# ManualBot.net
KiCad netlist of a schematic drawn in EAGLE
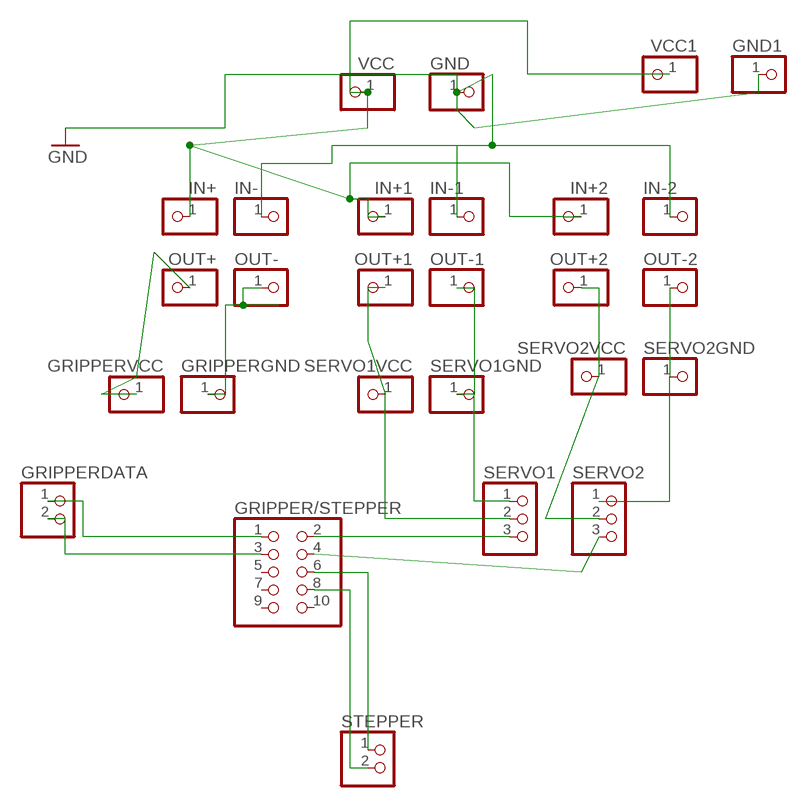
[diagram p0: schematic, sheet 1]

(export (version "E")
  (design (tool "Eeschema 10.0.6"))
  (components
    (comp (ref "GND")
      (value "PINHD-1X1")
      (footprint "eagle-import:1X01")
      (libsource (lib "eagle-import") (part "PINHD-1X1"))
    )
    (comp (ref "GND1")
      (value "PINHD-1X1")
      (footprint "eagle-import:1X01")
      (libsource (lib "eagle-import") (part "PINHD-1X1"))
    )
    (comp (ref "GRIPPER/STEPPER")
      (value "PINHD-2X5")
      (footprint "eagle-import:2X05")
      (libsource (lib "eagle-import") (part "PINHD-2X5"))
    )
    (comp (ref "GRIPPERDATA")
      (value "PINHD-1X2")
      (footprint "eagle-import:1X02")
      (libsource (lib "eagle-import") (part "PINHD-1X2"))
    )
    (comp (ref "GRIPPERGND")
      (value "PINHD-1X1")
      (footprint "eagle-import:1X01")
      (libsource (lib "eagle-import") (part "PINHD-1X1"))
    )
    (comp (ref "GRIPPERVCC")
      (value "PINHD-1X1")
      (footprint "eagle-import:1X01")
      (libsource (lib "eagle-import") (part "PINHD-1X1"))
    )
    (comp (ref "IN+")
      (value "PINHD-1X1")
      (footprint "eagle-import:1X01")
      (libsource (lib "eagle-import") (part "PINHD-1X1"))
    )
    (comp (ref "IN+1")
      (value "PINHD-1X1")
      (footprint "eagle-import:1X01")
      (libsource (lib "eagle-import") (part "PINHD-1X1"))
    )
    (comp (ref "IN+2")
      (value "PINHD-1X1")
      (footprint "eagle-import:1X01")
      (libsource (lib "eagle-import") (part "PINHD-1X1"))
    )
    (comp (ref "IN-")
      (value "PINHD-1X1")
      (footprint "eagle-import:1X01")
      (libsource (lib "eagle-import") (part "PINHD-1X1"))
    )
    (comp (ref "IN-1")
      (value "PINHD-1X1")
      (footprint "eagle-import:1X01")
      (libsource (lib "eagle-import") (part "PINHD-1X1"))
    )
    (comp (ref "IN-2")
      (value "PINHD-1X1")
      (footprint "eagle-import:1X01")
      (libsource (lib "eagle-import") (part "PINHD-1X1"))
    )
    (comp (ref "OUT+")
      (value "PINHD-1X1")
      (footprint "eagle-import:1X01")
      (libsource (lib "eagle-import") (part "PINHD-1X1"))
    )
    (comp (ref "OUT+1")
      (value "PINHD-1X1")
      (footprint "eagle-import:1X01")
      (libsource (lib "eagle-import") (part "PINHD-1X1"))
    )
    (comp (ref "OUT+2")
      (value "PINHD-1X1")
      (footprint "eagle-import:1X01")
      (libsource (lib "eagle-import") (part "PINHD-1X1"))
    )
    (comp (ref "OUT-")
      (value "PINHD-1X1")
      (footprint "eagle-import:1X01")
      (libsource (lib "eagle-import") (part "PINHD-1X1"))
    )
    (comp (ref "OUT-1")
      (value "PINHD-1X1")
      (footprint "eagle-import:1X01")
      (libsource (lib "eagle-import") (part "PINHD-1X1"))
    )
    (comp (ref "OUT-2")
      (value "PINHD-1X1")
      (footprint "eagle-import:1X01")
      (libsource (lib "eagle-import") (part "PINHD-1X1"))
    )
    (comp (ref "SERVO1")
      (value "PINHD-1X3")
      (footprint "eagle-import:1X03")
      (libsource (lib "eagle-import") (part "PINHD-1X3"))
    )
    (comp (ref "SERVO1GND")
      (value "PINHD-1X1")
      (footprint "eagle-import:1X01")
      (libsource (lib "eagle-import") (part "PINHD-1X1"))
    )
    (comp (ref "SERVO1VCC")
      (value "PINHD-1X1")
      (footprint "eagle-import:1X01")
      (libsource (lib "eagle-import") (part "PINHD-1X1"))
    )
    (comp (ref "SERVO2")
      (value "PINHD-1X3")
      (footprint "eagle-import:1X03")
      (libsource (lib "eagle-import") (part "PINHD-1X3"))
    )
    (comp (ref "SERVO2GND")
      (value "PINHD-1X1")
      (footprint "eagle-import:1X01")
      (libsource (lib "eagle-import") (part "PINHD-1X1"))
    )
    (comp (ref "SERVO2VCC")
      (value "PINHD-1X1")
      (footprint "eagle-import:1X01")
      (libsource (lib "eagle-import") (part "PINHD-1X1"))
    )
    (comp (ref "STEPPER")
      (value "PINHD-1X2")
      (footprint "eagle-import:1X02")
      (libsource (lib "eagle-import") (part "PINHD-1X2"))
    )
    (comp (ref "VCC")
      (value "PINHD-1X1")
      (footprint "eagle-import:1X01")
      (libsource (lib "eagle-import") (part "PINHD-1X1"))
    )
    (comp (ref "VCC1")
      (value "PINHD-1X1")
      (footprint "eagle-import:1X01")
      (libsource (lib "eagle-import") (part "PINHD-1X1"))
    )
  )
  (nets
    (net (code "1") (name "GND") (class "Default")
      (node (ref "GND") (pin "1") (pinfunction "1_1") (pintype "passive"))
      (node (ref "GND1") (pin "1") (pinfunction "1_1") (pintype "passive"))
      (node (ref "IN-") (pin "1") (pinfunction "1_1") (pintype "passive"))
      (node (ref "IN-1") (pin "1") (pinfunction "1_1") (pintype "passive"))
      (node (ref "IN-2") (pin "1") (pinfunction "1_1") (pintype "passive"))
    )
    (net (code "2") (name "Net-(GRIPPER/STEPPER-Pad1)") (class "Default")
      (node (ref "GRIPPER/STEPPER") (pin "1") (pinfunction "1_1") (pintype "passive"))
      (node (ref "GRIPPERDATA") (pin "1") (pinfunction "1_1") (pintype "passive"))
    )
    (net (code "3") (name "Net-(GRIPPER/STEPPER-Pad2)") (class "Default")
      (node (ref "GRIPPER/STEPPER") (pin "2") (pinfunction "2_2") (pintype "passive"))
      (node (ref "SERVO1") (pin "3") (pinfunction "3_3") (pintype "passive"))
    )
    (net (code "4") (name "Net-(GRIPPER/STEPPER-Pad3)") (class "Default")
      (node (ref "GRIPPER/STEPPER") (pin "3") (pinfunction "3_3") (pintype "passive"))
      (node (ref "GRIPPERDATA") (pin "2") (pinfunction "2_2") (pintype "passive"))
    )
    (net (code "5") (name "Net-(GRIPPER/STEPPER-Pad4)") (class "Default")
      (node (ref "GRIPPER/STEPPER") (pin "4") (pinfunction "4_4") (pintype "passive"))
      (node (ref "SERVO2") (pin "3") (pinfunction "3_3") (pintype "passive"))
    )
    (net (code "6") (name "Net-(GRIPPER/STEPPER-Pad6)") (class "Default")
      (node (ref "GRIPPER/STEPPER") (pin "6") (pinfunction "6_6") (pintype "passive"))
      (node (ref "STEPPER") (pin "1") (pinfunction "1_1") (pintype "passive"))
    )
    (net (code "7") (name "Net-(GRIPPER/STEPPER-Pad8)") (class "Default")
      (node (ref "GRIPPER/STEPPER") (pin "8") (pinfunction "8_8") (pintype "passive"))
      (node (ref "STEPPER") (pin "2") (pinfunction "2_2") (pintype "passive"))
    )
    (net (code "8") (name "Net-(GRIPPERGND-Pad1)") (class "Default")
      (node (ref "GRIPPERGND") (pin "1") (pinfunction "1_1") (pintype "passive"))
      (node (ref "OUT-") (pin "1") (pinfunction "1_1") (pintype "passive"))
    )
    (net (code "9") (name "Net-(GRIPPERVCC-Pad1)") (class "Default")
      (node (ref "GRIPPERVCC") (pin "1") (pinfunction "1_1") (pintype "passive"))
      (node (ref "OUT+") (pin "1") (pinfunction "1_1") (pintype "passive"))
    )
    (net (code "10") (name "Net-(IN+-Pad1)") (class "Default")
      (node (ref "IN+") (pin "1") (pinfunction "1_1") (pintype "passive"))
      (node (ref "IN+1") (pin "1") (pinfunction "1_1") (pintype "passive"))
      (node (ref "IN+2") (pin "1") (pinfunction "1_1") (pintype "passive"))
      (node (ref "VCC") (pin "1") (pinfunction "1_1") (pintype "passive"))
      (node (ref "VCC1") (pin "1") (pinfunction "1_1") (pintype "passive"))
    )
    (net (code "11") (name "Net-(OUT+1-Pad1)") (class "Default")
      (node (ref "OUT+1") (pin "1") (pinfunction "1_1") (pintype "passive"))
      (node (ref "SERVO1") (pin "2") (pinfunction "2_2") (pintype "passive"))
      (node (ref "SERVO1VCC") (pin "1") (pinfunction "1_1") (pintype "passive"))
    )
    (net (code "12") (name "Net-(OUT+2-Pad1)") (class "Default")
      (node (ref "OUT+2") (pin "1") (pinfunction "1_1") (pintype "passive"))
      (node (ref "SERVO2") (pin "2") (pinfunction "2_2") (pintype "passive"))
      (node (ref "SERVO2VCC") (pin "1") (pinfunction "1_1") (pintype "passive"))
    )
    (net (code "13") (name "Net-(OUT-1-Pad1)") (class "Default")
      (node (ref "OUT-1") (pin "1") (pinfunction "1_1") (pintype "passive"))
      (node (ref "SERVO1") (pin "1") (pinfunction "1_1") (pintype "passive"))
      (node (ref "SERVO1GND") (pin "1") (pinfunction "1_1") (pintype "passive"))
    )
    (net (code "14") (name "Net-(OUT-2-Pad1)") (class "Default")
      (node (ref "OUT-2") (pin "1") (pinfunction "1_1") (pintype "passive"))
      (node (ref "SERVO2") (pin "1") (pinfunction "1_1") (pintype "passive"))
      (node (ref "SERVO2GND") (pin "1") (pinfunction "1_1") (pintype "passive"))
    )
    (net (code "15") (name "unconnected-(GRIPPER/STEPPER-Pad5)") (class "Default")
      (node (ref "GRIPPER/STEPPER") (pin "5") (pinfunction "5_5") (pintype "passive"))
    )
    (net (code "16") (name "unconnected-(GRIPPER/STEPPER-Pad7)") (class "Default")
      (node (ref "GRIPPER/STEPPER") (pin "7") (pinfunction "7_7") (pintype "passive"))
    )
    (net (code "17") (name "unconnected-(GRIPPER/STEPPER-Pad9)") (class "Default")
      (node (ref "GRIPPER/STEPPER") (pin "9") (pinfunction "9_9") (pintype "passive"))
    )
    (net (code "18") (name "unconnected-(GRIPPER/STEPPER-Pad10)") (class "Default")
      (node (ref "GRIPPER/STEPPER") (pin "10") (pinfunction "10_10") (pintype "passive"))
    )
  )
)
